# Audio_Input_Mic_Array.net
KiCad netlist of a schematic drawn in Altium Designer
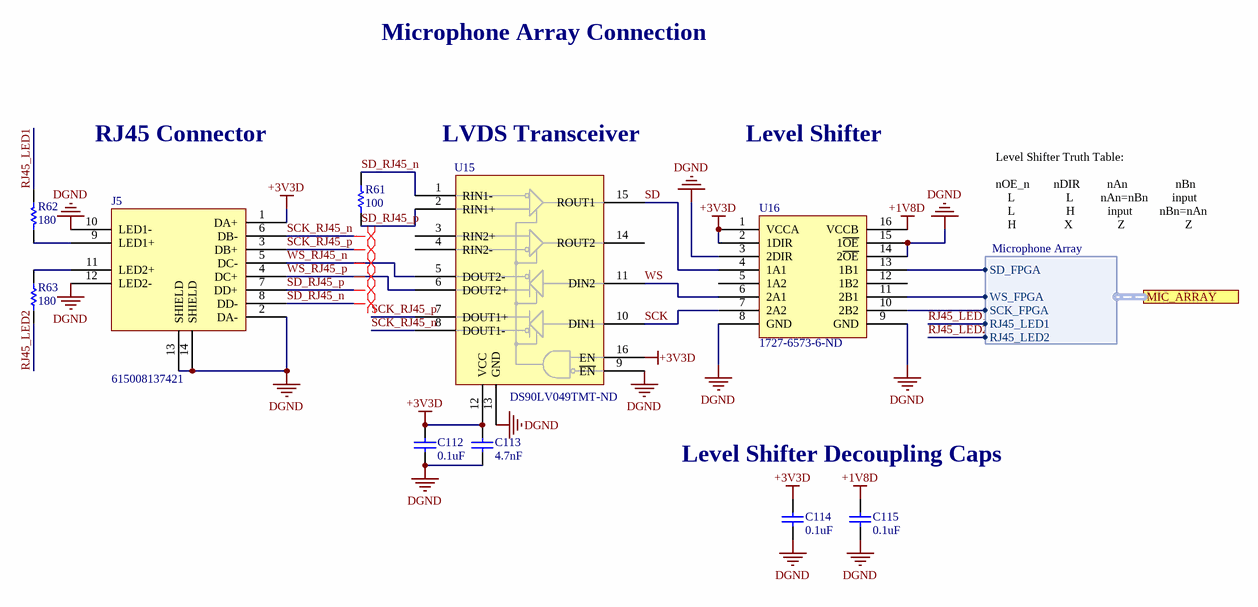
[diagram p0: Audio_Input_Mic_Array.SchDoc]

(export (version "E")
  (design (tool "Eeschema 10.0.6"))
  (components
    (comp (ref "C112")
      (value "CL10F104ZO8NNNC")
      (footprint "3-0603_L")
      (description "CAP CER 0.1UF 16V Y5V 0603")
      (fields
        (field (name "MANUFACTURER") "Samsung")
        (field (name "TOLERANCE") "80%")
        (field (name "CAPACITANCE") "0.1uF")
      )
      (libsource (lib "Schematic_Components_CD") (part "CL10F104ZO8NNNC"))
    )
    (comp (ref "C113")
      (value "C0603C472K8RACTU")
      (footprint "3-0603_L")
      (description "CAP CER 4700PF 10V X7R 0603")
      (fields
        (field (name "MANUFACTURER") "KEMET")
        (field (name "TOLERANCE") "10%")
        (field (name "CAPACITANCE") "4.7nF")
      )
      (libsource (lib "Schematic_Components_CD") (part "C0603C472K8RACTU"))
    )
    (comp (ref "C114")
      (value "CL10F104ZO8NNNC")
      (footprint "3-0603_L")
      (description "CAP CER 0.1UF 16V Y5V 0603")
      (fields
        (field (name "MANUFACTURER") "Samsung")
        (field (name "TOLERANCE") "80%")
        (field (name "CAPACITANCE") "0.1uF")
      )
      (libsource (lib "Schematic_Components_CD") (part "CL10F104ZO8NNNC"))
    )
    (comp (ref "C115")
      (value "CL10F104ZO8NNNC")
      (footprint "3-0603_L")
      (description "CAP CER 0.1UF 16V Y5V 0603")
      (fields
        (field (name "MANUFACTURER") "Samsung")
        (field (name "TOLERANCE") "80%")
        (field (name "CAPACITANCE") "0.1uF")
      )
      (libsource (lib "Schematic_Components_CD") (part "CL10F104ZO8NNNC"))
    )
    (comp (ref "J5")
      (value "CONN MOD JACK 8P8C R/A SHIELDED")
      (footprint "RJ45")
      (description "Jack Modular Connector 8p8c (RJ45, Ethernet) 90° Angle (Right) Shielded, EMI Finger Cat5")
      (fields
        (field (name "MANUFACTURER") "Wurth Electronics")
        (field (name "MANUFACTURER PART NUMBER") "615008137421")
      )
      (libsource (lib "Schematic_Components_CD") (part "615008137421"))
    )
    (comp (ref "R61")
      (value "ERA-3AEB101V")
      (footprint "3-0603_R_L")
      (description "RES SMD 100 OHM 0.1% 1/10W 0603")
      (fields
        (field (name "MANUFACTURER") "Panasonic ECG")
        (field (name "TOLERANCE") "0.1%")
        (field (name "RESISTANCE") "100")
      )
      (libsource (lib "Schematic_Components_CD") (part "ERA-3AEB101V"))
    )
    (comp (ref "R62")
      (value "ERA-3AEB181V")
      (footprint "3-0603_R_L")
      (description "RES SMD 180 OHM 0.1% 1/10W 0603")
      (fields
        (field (name "MANUFACTURER") "Panasonic")
        (field (name "MANUFACTURER PART NUMBER") "ERA3AEB181V")
        (field (name "RESISTANCE") "180")
      )
      (libsource (lib "Schematic_Components_CD") (part "ERA-3AEB181V"))
    )
    (comp (ref "R63")
      (value "ERA-3AEB181V")
      (footprint "3-0603_R_L")
      (description "RES SMD 180 OHM 0.1% 1/10W 0603")
      (fields
        (field (name "MANUFACTURER") "Panasonic")
        (field (name "MANUFACTURER PART NUMBER") "ERA3AEB181V")
        (field (name "RESISTANCE") "180")
      )
      (libsource (lib "Schematic_Components_CD") (part "ERA-3AEB181V"))
    )
    (comp (ref "U15")
      (value "DS90LV049TMT")
      (footprint "TSOP65P640X120-16N")
      (description "IC LDVR/RCVR PAIR LVDS 16TSSOP")
      (fields
        (field (name "MANUFACTURER") "TI National Semiconductor")
        (field (name "SUPPLIER PART NUMBER 1") "DS90LV049TMT-ND")
      )
      (libsource (lib "Schematic_Components_CD") (part "DS90LV049TMT"))
    )
    (comp (ref "U16")
      (value "IC TXRX 4BIT DUAL 3ST 16TSSOP")
      (footprint "TSOP65P640X120-16N")
      (description "Voltage Level Translator Bidirectional 2 Circuit 2 Channel 380Mbps 16-TSSOP")
      (fields
        (field (name "MANUFACTURER") "NXP Semiconductors")
        (field (name "SUPPLIER PART NUMBER 1") "1727-6573-6-ND")
        (field (name "MANUFACTURER PART NUMBER") "74AVC4T245PW,118")
      )
      (libsource (lib "Schematic_Components_CD") (part "74AVC4T245PW,118"))
    )
  )
  (nets
    (net (code "3") (name "+1V8D") (class "Default")
      (node (ref "C115") (pin "1") (pinfunction "1_1") (pintype "passive"))
      (node (ref "U16") (pin "16") (pinfunction "VCCB_16") (pintype "passive"))
    )
    (net (code "4") (name "+3V3D") (class "Default")
      (node (ref "C112") (pin "1") (pinfunction "1_1") (pintype "passive"))
      (node (ref "C113") (pin "2") (pinfunction "2_2") (pintype "passive"))
      (node (ref "C114") (pin "1") (pinfunction "1_1") (pintype "passive"))
      (node (ref "J5") (pin "1") (pinfunction "DA+_1") (pintype "passive"))
      (node (ref "U15") (pin "12") (pinfunction "VCC_12") (pintype "power_in"))
      (node (ref "U15") (pin "16") (pinfunction "EN_16") (pintype "passive"))
      (node (ref "U16") (pin "1") (pinfunction "VCCA_1") (pintype "passive"))
      (node (ref "U16") (pin "2") (pinfunction "1DIR_2") (pintype "passive"))
    )
    (net (code "5") (name "/RJ45_LED1") (class "Default")
      (node (ref "R62") (pin "1") (pinfunction "1_1") (pintype "passive"))
    )
    (net (code "6") (name "/RJ45_LED2") (class "Default")
      (node (ref "R63") (pin "1") (pinfunction "1_1") (pintype "passive"))
    )
    (net (code "7") (name "/SCK") (class "Default")
      (node (ref "U15") (pin "10") (pinfunction "DIN1_10") (pintype "passive"))
      (node (ref "U16") (pin "7") (pinfunction "2A2_7") (pintype "passive"))
    )
    (net (code "8") (name "/SCK_FPGA") (class "Default")
      (node (ref "U16") (pin "10") (pinfunction "2B2_10") (pintype "passive"))
    )
    (net (code "9") (name "/SCK_RJ45_n") (class "Default")
      (node (ref "J5") (pin "6") (pinfunction "DB-_6") (pintype "passive"))
      (node (ref "U15") (pin "8") (pinfunction "DOUT1-_8") (pintype "passive"))
    )
    (net (code "10") (name "/SCK_RJ45_p") (class "Default")
      (node (ref "J5") (pin "3") (pinfunction "DB+_3") (pintype "passive"))
      (node (ref "U15") (pin "7") (pinfunction "DOUT1+_7") (pintype "passive"))
    )
    (net (code "11") (name "/SD") (class "Default")
      (node (ref "U15") (pin "15") (pinfunction "ROUT1_15") (pintype "passive"))
      (node (ref "U16") (pin "4") (pinfunction "1A1_4") (pintype "passive"))
    )
    (net (code "12") (name "/SD_FPGA") (class "Default")
      (node (ref "U16") (pin "13") (pinfunction "1B1_13") (pintype "passive"))
    )
    (net (code "13") (name "/SD_RJ45_n") (class "Default")
      (node (ref "J5") (pin "8") (pinfunction "DD-_8") (pintype "passive"))
      (node (ref "R61") (pin "2") (pinfunction "2_2") (pintype "passive"))
      (node (ref "U15") (pin "1") (pinfunction "RIN1-_1") (pintype "passive"))
    )
    (net (code "14") (name "/SD_RJ45_p") (class "Default")
      (node (ref "J5") (pin "7") (pinfunction "DD+_7") (pintype "passive"))
      (node (ref "R61") (pin "1") (pinfunction "1_1") (pintype "passive"))
      (node (ref "U15") (pin "2") (pinfunction "RIN1+_2") (pintype "passive"))
    )
    (net (code "15") (name "/WS") (class "Default")
      (node (ref "U15") (pin "11") (pinfunction "DIN2_11") (pintype "passive"))
      (node (ref "U16") (pin "6") (pinfunction "2A1_6") (pintype "passive"))
    )
    (net (code "16") (name "/WS_FPGA") (class "Default")
      (node (ref "U16") (pin "11") (pinfunction "2B1_11") (pintype "passive"))
    )
    (net (code "17") (name "/WS_RJ45_n") (class "Default")
      (node (ref "J5") (pin "5") (pinfunction "DC-_5") (pintype "passive"))
      (node (ref "U15") (pin "5") (pinfunction "DOUT2-_5") (pintype "passive"))
    )
    (net (code "18") (name "/WS_RJ45_p") (class "Default")
      (node (ref "J5") (pin "4") (pinfunction "DC+_4") (pintype "passive"))
      (node (ref "U15") (pin "6") (pinfunction "DOUT2+_6") (pintype "passive"))
    )
    (net (code "20") (name "DGND") (class "Default")
      (node (ref "C112") (pin "2") (pinfunction "2_2") (pintype "passive"))
      (node (ref "C113") (pin "1") (pinfunction "1_1") (pintype "passive"))
      (node (ref "C114") (pin "2") (pinfunction "2_2") (pintype "passive"))
      (node (ref "C115") (pin "2") (pinfunction "2_2") (pintype "passive"))
      (node (ref "J5") (pin "10") (pinfunction "LED1-_10") (pintype "passive"))
      (node (ref "J5") (pin "12") (pinfunction "LED2-_12") (pintype "passive"))
      (node (ref "J5") (pin "13") (pinfunction "SHIELD_13") (pintype "passive"))
      (node (ref "J5") (pin "14") (pinfunction "SHIELD_14") (pintype "passive"))
      (node (ref "J5") (pin "2") (pinfunction "DA-_2") (pintype "passive"))
      (node (ref "U15") (pin "13") (pinfunction "GND_13") (pintype "power_in"))
      (node (ref "U15") (pin "9") (pinfunction "~{EN}_9") (pintype "passive"))
      (node (ref "U16") (pin "14") (pinfunction "2~{OE}_14") (pintype "passive"))
      (node (ref "U16") (pin "15") (pinfunction "1~{OE}_15") (pintype "passive"))
      (node (ref "U16") (pin "3") (pinfunction "2DIR_3") (pintype "passive"))
      (node (ref "U16") (pin "8") (pinfunction "GND_8") (pintype "passive"))
      (node (ref "U16") (pin "9") (pinfunction "GND_9") (pintype "passive"))
    )
    (net (code "21") (name "Net-(J5-LED1+)") (class "Default")
      (node (ref "J5") (pin "9") (pinfunction "LED1+_9") (pintype "passive"))
      (node (ref "R62") (pin "2") (pinfunction "2_2") (pintype "passive"))
    )
    (net (code "22") (name "Net-(J5-LED2+)") (class "Default")
      (node (ref "J5") (pin "11") (pinfunction "LED2+_11") (pintype "passive"))
      (node (ref "R63") (pin "2") (pinfunction "2_2") (pintype "passive"))
    )
    (net (code "23") (name "unconnected-(U15-RIN2+-Pad3)") (class "Default")
      (node (ref "U15") (pin "3") (pinfunction "RIN2+_3") (pintype "passive"))
    )
    (net (code "24") (name "unconnected-(U15-RIN2--Pad4)") (class "Default")
      (node (ref "U15") (pin "4") (pinfunction "RIN2-_4") (pintype "passive"))
    )
    (net (code "25") (name "unconnected-(U15-ROUT2-Pad14)") (class "Default")
      (node (ref "U15") (pin "14") (pinfunction "ROUT2_14") (pintype "passive"))
    )
    (net (code "26") (name "unconnected-(U16-1A2-Pad5)") (class "Default")
      (node (ref "U16") (pin "5") (pinfunction "1A2_5") (pintype "passive"))
    )
    (net (code "27") (name "unconnected-(U16-1B2-Pad12)") (class "Default")
      (node (ref "U16") (pin "12") (pinfunction "1B2_12") (pintype "passive"))
    )
  )
)
